# OpenRing_Haptic.net
KiCad netlist of a schematic drawn in Altium Designer
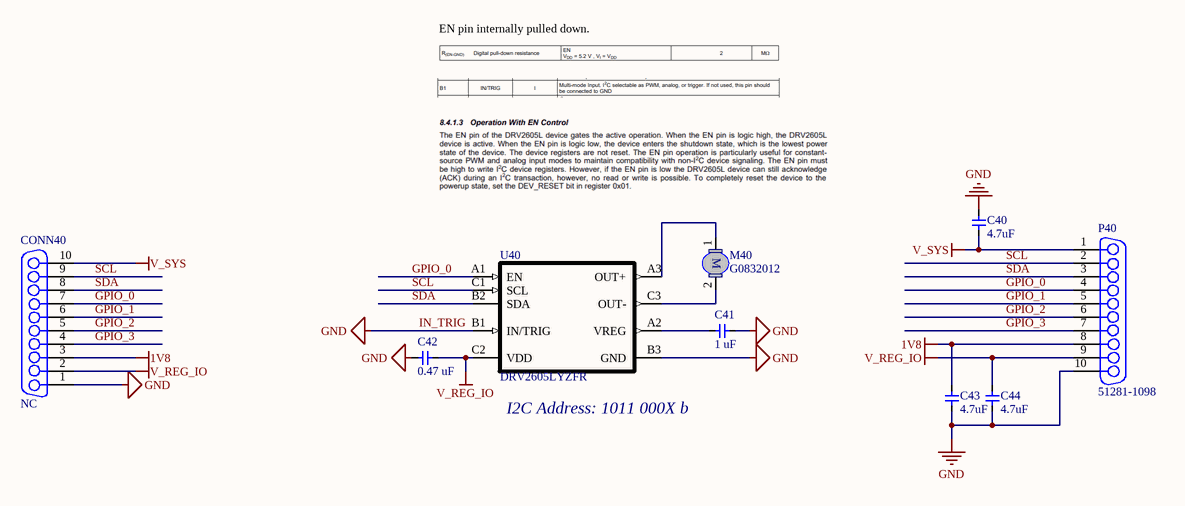
[diagram p0: OpenRing_Haptic.SchDoc]

(export (version "E")
  (design (tool "Eeschema 10.0.6"))
  (components
    (comp (ref "C40")
      (value "4.7uF")
      (footprint "CAPC1005X05N")
      (description "Multilayer Ceramic Capacitor, 4.7 uF, 10 V, ± 20%, X5R, 0402 [1005 Metric]")
      (fields
        (field (name "MANUFACTURER") "Murata")
        (field (name "MANUFACTURER PART NUMBER") "GRM155R61A475MEAAD")
      )
      (libsource (lib "OpenRingComponents") (part "GRM155R61A475MEAAD"))
    )
    (comp (ref "C41")
      (value "1 uF")
      (footprint "CAPC1005X05N")
      (description "CAP CER 1UF 10V X5R 0402")
      (fields
        (field (name "MANUFACTURER") "Murata Electronics North America")
        (field (name "MANUFACTURER PART NUMBER") "GRM155R61A105KE15D")
      )
      (libsource (lib "OpenRingComponents") (part "GRM155R61A105KE15D"))
    )
    (comp (ref "C42")
      (value "0.47 uF")
      (footprint "CAPC1005X05N")
      (description "CAP CER 0.47UF 10V X5R 0402")
      (fields
        (field (name "MANUFACTURER") "Murata Electronics North America")
        (field (name "MANUFACTURER PART NUMBER") "GRM155R61A474KE15D")
      )
      (libsource (lib "OpenRingComponents") (part "GRM155R61A474KE15D"))
    )
    (comp (ref "C43")
      (value "4.7uF")
      (footprint "CAPC1005X05N")
      (description "Multilayer Ceramic Capacitor, 4.7 uF, 10 V, ± 20%, X5R, 0402 [1005 Metric]")
      (fields
        (field (name "MANUFACTURER") "Murata")
        (field (name "MANUFACTURER PART NUMBER") "GRM155R61A475MEAAD")
      )
      (libsource (lib "OpenRingComponents") (part "GRM155R61A475MEAAD"))
    )
    (comp (ref "C44")
      (value "4.7uF")
      (footprint "CAPC1005X05N")
      (description "Multilayer Ceramic Capacitor, 4.7 uF, 10 V, ± 20%, X5R, 0402 [1005 Metric]")
      (fields
        (field (name "MANUFACTURER") "Murata")
        (field (name "MANUFACTURER PART NUMBER") "GRM155R61A475MEAAD")
      )
      (libsource (lib "OpenRingComponents") (part "GRM155R61A475MEAAD"))
    )
    (comp (ref "CONN40")
      (value "NC")
      (footprint "51281-1098-PCB")
      (libsource (lib "Connectors") (part "51281-1098-PCB"))
    )
    (comp (ref "M40")
      (value "G0832012")
      (footprint "G0832012")
      (description "VIBRATION MOTOR 1.8V")
      (fields (field (name "MANUFACTURER") "Jinlong Machinery & Electronics, Inc."))
      (libsource (lib "OpenRingComponents") (part "G0832012"))
    )
    (comp (ref "P40")
      (value "51281-1098")
      (footprint "51281-1098")
      (description "FFC/FPC Connector, Surface Mount, Right-Angle, Non-ZIF, Dual Contact Style")
      (fields (field (name "MANUFACTURER") "Molex"))
      (libsource (lib "Connectors") (part "51281-1098"))
    )
    (comp (ref "U40")
      (value "DRV2605LYZFR")
      (footprint "BGA9C50P3X3_144X144X62")
      (fields (field (name "MANUFACTURER") "Texas Instruments"))
      (libsource (lib "OpenRingComponents") (part "DRV2605LYZFR"))
    )
  )
  (nets
    (net (code "1") (name "/GPIO_0") (class "Default")
      (node (ref "CONN40") (pin "7") (pinfunction "7_7") (pintype "passive"))
      (node (ref "P40") (pin "4") (pinfunction "4_4") (pintype "passive"))
      (node (ref "U40") (pin "A1") (pinfunction "EN_A1") (pintype "input"))
    )
    (net (code "2") (name "/GPIO_1") (class "Default")
      (node (ref "CONN40") (pin "6") (pinfunction "6_6") (pintype "passive"))
      (node (ref "P40") (pin "5") (pinfunction "5_5") (pintype "passive"))
    )
    (net (code "3") (name "/GPIO_2") (class "Default")
      (node (ref "CONN40") (pin "5") (pinfunction "5_5") (pintype "passive"))
      (node (ref "P40") (pin "6") (pinfunction "6_6") (pintype "passive"))
    )
    (net (code "4") (name "/GPIO_3") (class "Default")
      (node (ref "CONN40") (pin "4") (pinfunction "4_4") (pintype "passive"))
      (node (ref "P40") (pin "7") (pinfunction "7_7") (pintype "passive"))
    )
    (net (code "5") (name "/SCL") (class "Default")
      (node (ref "CONN40") (pin "9") (pinfunction "9_9") (pintype "passive"))
      (node (ref "P40") (pin "2") (pinfunction "2_2") (pintype "passive"))
      (node (ref "U40") (pin "C1") (pinfunction "SCL_C1") (pintype "input"))
    )
    (net (code "6") (name "/SDA") (class "Default")
      (node (ref "CONN40") (pin "8") (pinfunction "8_8") (pintype "passive"))
      (node (ref "P40") (pin "3") (pinfunction "3_3") (pintype "passive"))
      (node (ref "U40") (pin "B2") (pinfunction "SDA_B2") (pintype "passive"))
    )
    (net (code "7") (name "1V8") (class "Default")
      (node (ref "C43") (pin "2") (pinfunction "2_2") (pintype "passive"))
      (node (ref "CONN40") (pin "3") (pinfunction "3_3") (pintype "passive"))
      (node (ref "P40") (pin "8") (pinfunction "8_8") (pintype "passive"))
    )
    (net (code "8") (name "GND") (class "Default")
      (node (ref "C40") (pin "2") (pinfunction "2_2") (pintype "passive"))
      (node (ref "C41") (pin "1") (pinfunction "1_1") (pintype "passive"))
      (node (ref "C42") (pin "2") (pinfunction "2_2") (pintype "passive"))
      (node (ref "C43") (pin "1") (pinfunction "1_1") (pintype "passive"))
      (node (ref "C44") (pin "1") (pinfunction "1_1") (pintype "passive"))
      (node (ref "CONN40") (pin "1") (pinfunction "1_1") (pintype "passive"))
      (node (ref "P40") (pin "10") (pinfunction "10_10") (pintype "passive"))
      (node (ref "U40") (pin "B1") (pinfunction "IN/TRIG_B1") (pintype "input"))
      (node (ref "U40") (pin "B3") (pinfunction "GND_B3") (pintype "power_in"))
    )
    (net (code "9") (name "Net-(U40-OUT+)") (class "Default")
      (node (ref "M40") (pin "1") (pinfunction "V+_1") (pintype "passive"))
      (node (ref "U40") (pin "A3") (pinfunction "OUT+_A3") (pintype "output"))
    )
    (net (code "10") (name "Net-(U40-OUT-)") (class "Default")
      (node (ref "M40") (pin "2") (pinfunction "V+_2") (pintype "passive"))
      (node (ref "U40") (pin "C3") (pinfunction "OUT-_C3") (pintype "output"))
    )
    (net (code "11") (name "Net-(U40-VREG)") (class "Default")
      (node (ref "C41") (pin "2") (pinfunction "2_2") (pintype "passive"))
      (node (ref "U40") (pin "A2") (pinfunction "VREG_A2") (pintype "output"))
    )
    (net (code "12") (name "V_REG_IO") (class "Default")
      (node (ref "C42") (pin "1") (pinfunction "1_1") (pintype "passive"))
      (node (ref "C44") (pin "2") (pinfunction "2_2") (pintype "passive"))
      (node (ref "CONN40") (pin "2") (pinfunction "2_2") (pintype "passive"))
      (node (ref "P40") (pin "9") (pinfunction "9_9") (pintype "passive"))
      (node (ref "U40") (pin "C2") (pinfunction "VDD_C2") (pintype "power_in"))
    )
    (net (code "13") (name "V_SYS") (class "Default")
      (node (ref "C40") (pin "1") (pinfunction "1_1") (pintype "passive"))
      (node (ref "CONN40") (pin "10") (pinfunction "10_10") (pintype "passive"))
      (node (ref "P40") (pin "1") (pinfunction "1_1") (pintype "passive"))
    )
  )
)
